# Strain_Gauge_Amplifier2.net
KiCad netlist of a schematic drawn in EAGLE
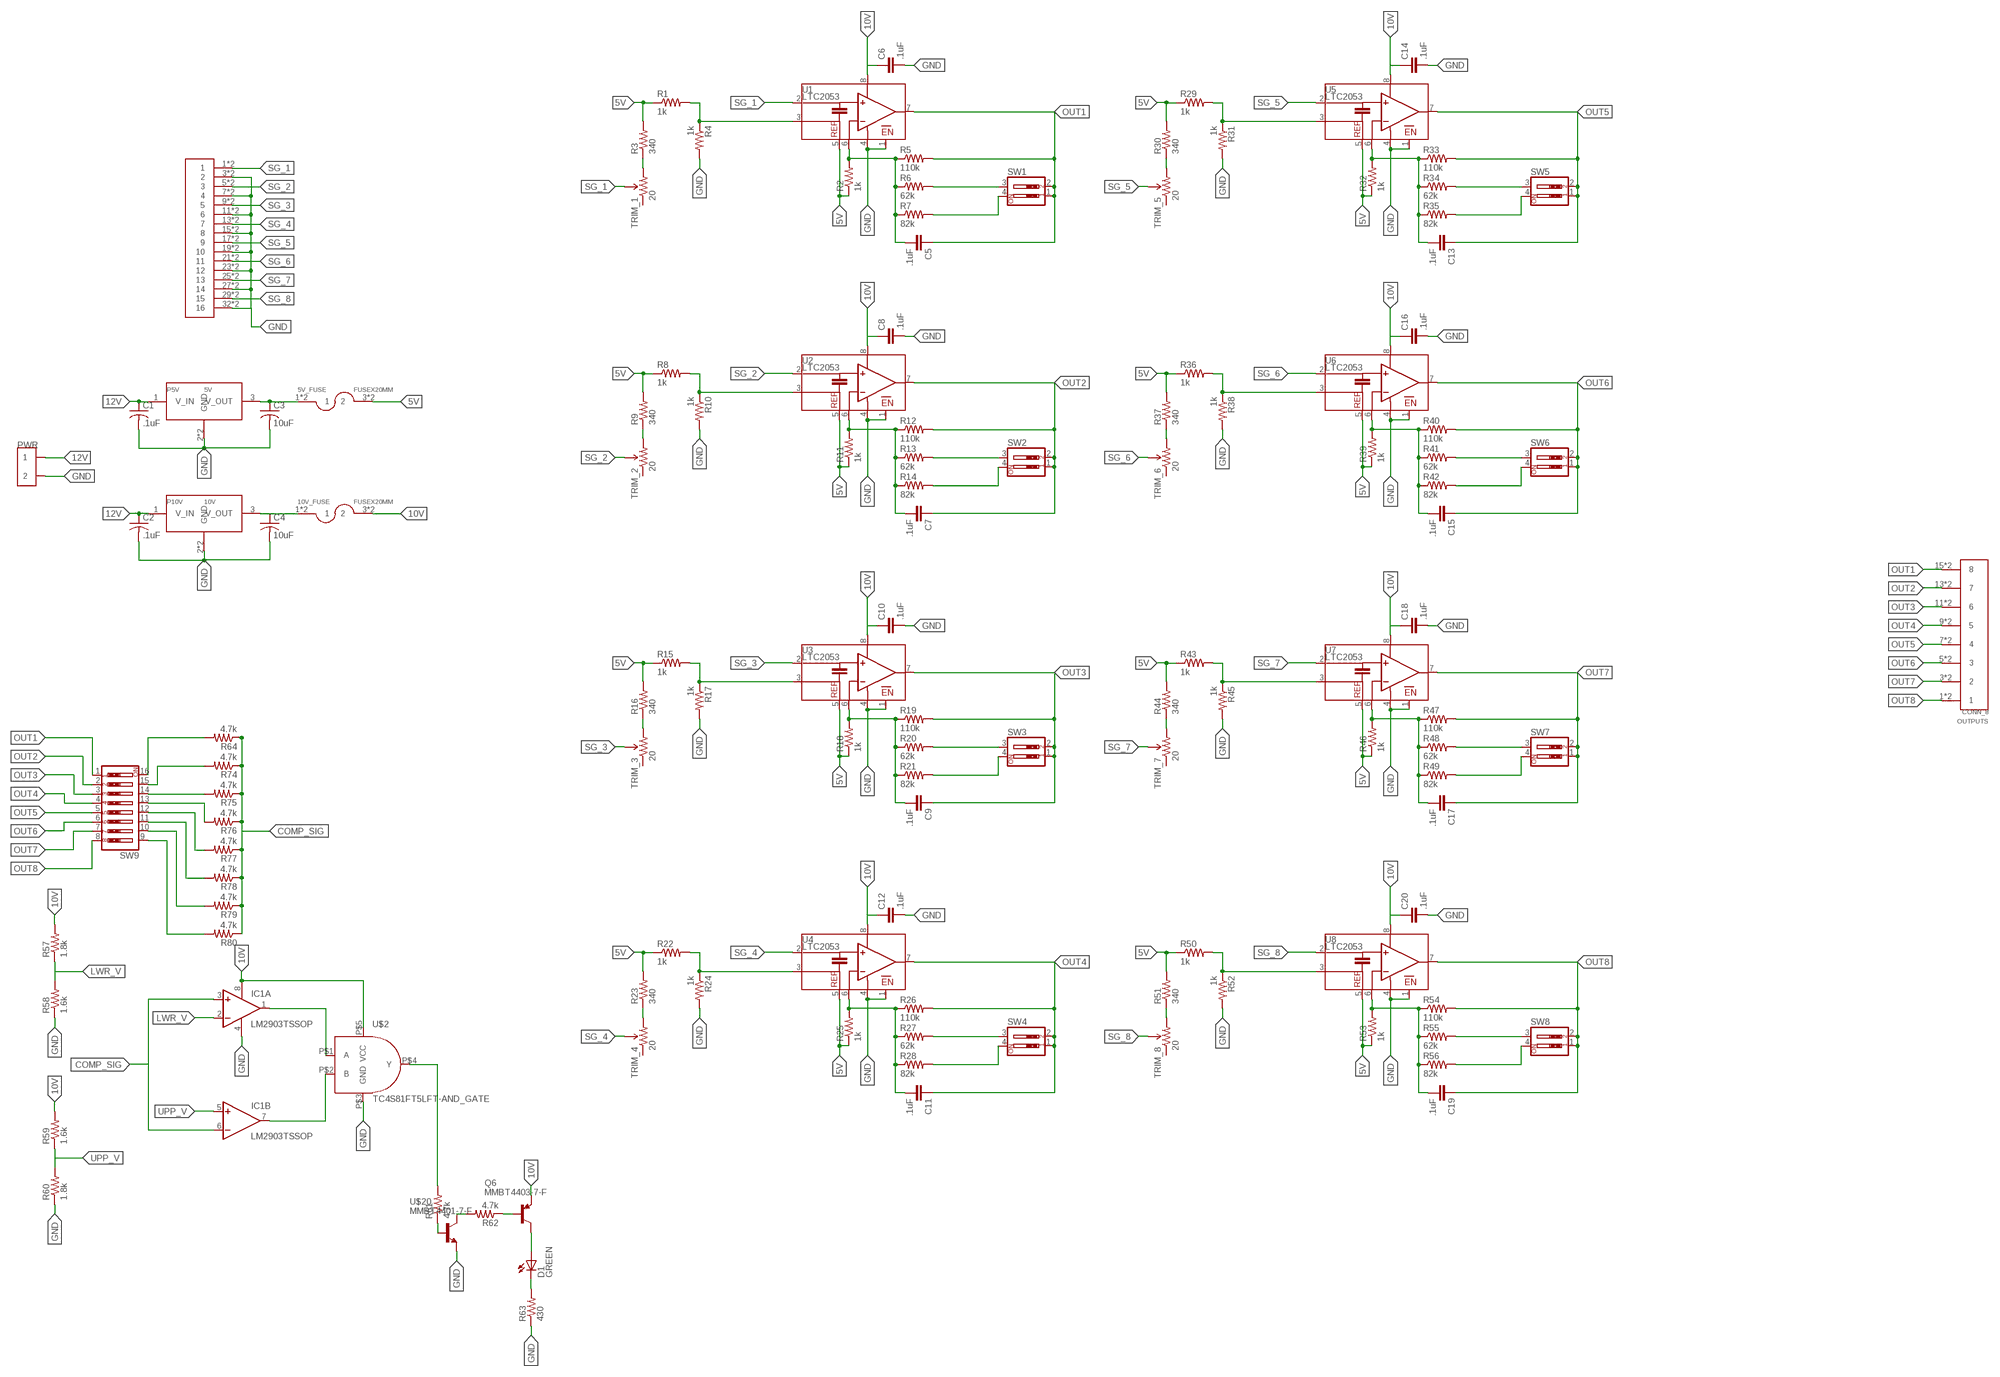
[diagram p0: schematic, sheet 1]

(export (version "E")
  (design (tool "Eeschema 10.0.6"))
  (components
    (comp (ref "5V_FUSE")
      (value "FUSEX20MM")
      (footprint "eagle-import:FUSE_5MM")
      (libsource (lib "eagle-import") (part "FUSEX20MM"))
    )
    (comp (ref "10V_FUSE")
      (value "FUSEX20MM")
      (footprint "eagle-import:FUSE_5MM")
      (libsource (lib "eagle-import") (part "FUSEX20MM"))
    )
    (comp (ref "C1")
      (value ".1uF")
      (footprint "eagle-import:C0603")
      (libsource (lib "eagle-import") (part "C-USC0603"))
    )
    (comp (ref "C2")
      (value ".1uF")
      (footprint "eagle-import:C0603")
      (libsource (lib "eagle-import") (part "C-USC0603"))
    )
    (comp (ref "C3")
      (value "10uF")
      (footprint "eagle-import:C1206")
      (libsource (lib "eagle-import") (part "C-USC1206"))
    )
    (comp (ref "C4")
      (value "10uF")
      (footprint "eagle-import:C1206")
      (libsource (lib "eagle-import") (part "C-USC1206"))
    )
    (comp (ref "C5")
      (value ".1uF")
      (footprint "eagle-import:0603-CAP")
      (libsource (lib "eagle-import") (part "CAP0603-CAP"))
    )
    (comp (ref "C6")
      (value ".1uF")
      (footprint "eagle-import:0603-CAP")
      (libsource (lib "eagle-import") (part "CAP0603-CAP"))
    )
    (comp (ref "C7")
      (value ".1uF")
      (footprint "eagle-import:0603-CAP")
      (libsource (lib "eagle-import") (part "CAP0603-CAP"))
    )
    (comp (ref "C8")
      (value ".1uF")
      (footprint "eagle-import:0603-CAP")
      (libsource (lib "eagle-import") (part "CAP0603-CAP"))
    )
    (comp (ref "C9")
      (value ".1uF")
      (footprint "eagle-import:0603-CAP")
      (libsource (lib "eagle-import") (part "CAP0603-CAP"))
    )
    (comp (ref "C10")
      (value ".1uF")
      (footprint "eagle-import:0603-CAP")
      (libsource (lib "eagle-import") (part "CAP0603-CAP"))
    )
    (comp (ref "C11")
      (value ".1uF")
      (footprint "eagle-import:0603-CAP")
      (libsource (lib "eagle-import") (part "CAP0603-CAP"))
    )
    (comp (ref "C12")
      (value ".1uF")
      (footprint "eagle-import:0603-CAP")
      (libsource (lib "eagle-import") (part "CAP0603-CAP"))
    )
    (comp (ref "C13")
      (value ".1uF")
      (footprint "eagle-import:0603-CAP")
      (libsource (lib "eagle-import") (part "CAP0603-CAP"))
    )
    (comp (ref "C14")
      (value ".1uF")
      (footprint "eagle-import:0603-CAP")
      (libsource (lib "eagle-import") (part "CAP0603-CAP"))
    )
    (comp (ref "C15")
      (value ".1uF")
      (footprint "eagle-import:0603-CAP")
      (libsource (lib "eagle-import") (part "CAP0603-CAP"))
    )
    (comp (ref "C16")
      (value ".1uF")
      (footprint "eagle-import:0603-CAP")
      (libsource (lib "eagle-import") (part "CAP0603-CAP"))
    )
    (comp (ref "C17")
      (value ".1uF")
      (footprint "eagle-import:0603-CAP")
      (libsource (lib "eagle-import") (part "CAP0603-CAP"))
    )
    (comp (ref "C18")
      (value ".1uF")
      (footprint "eagle-import:0603-CAP")
      (libsource (lib "eagle-import") (part "CAP0603-CAP"))
    )
    (comp (ref "C19")
      (value ".1uF")
      (footprint "eagle-import:0603-CAP")
      (libsource (lib "eagle-import") (part "CAP0603-CAP"))
    )
    (comp (ref "C20")
      (value ".1uF")
      (footprint "eagle-import:0603-CAP")
      (libsource (lib "eagle-import") (part "CAP0603-CAP"))
    )
    (comp (ref "D1")
      (value "GREEN")
      (footprint "eagle-import:LED-0603")
      (libsource (lib "eagle-import") (part "LED-GREEN0603"))
    )
    (comp (ref "IC1")
      (value "LM2903TSSOP")
      (footprint "eagle-import:TSSOP8")
      (libsource (lib "eagle-import") (part "LM2903TSSOP"))
    )
    (comp (ref "OUTPUTS")
      (value "CONN_8")
      (footprint "eagle-import:CONNECTOR_8")
      (libsource (lib "eagle-import") (part "CONN_8"))
    )
    (comp (ref "P5V")
      (value "5V")
      (footprint "eagle-import:SOT223")
      (libsource (lib "eagle-import") (part "LM2937"))
    )
    (comp (ref "P10V")
      (value "10V")
      (footprint "eagle-import:SOT223")
      (libsource (lib "eagle-import") (part "LM2937"))
    )
    (comp (ref "PWR")
      (value "CONN_2")
      (footprint "eagle-import:CONNECTOR_2")
      (libsource (lib "eagle-import") (part "CONN_2"))
    )
    (comp (ref "Q6")
      (value "MMBT4403-7-F")
      (footprint "eagle-import:SOT-23-3")
      (libsource (lib "eagle-import") (part "MMBT4403-7-F"))
    )
    (comp (ref "R1")
      (value "1k")
      (footprint "eagle-import:0603-RES")
      (libsource (lib "eagle-import") (part "RESISTOR0603"))
    )
    (comp (ref "R2")
      (value "1k")
      (footprint "eagle-import:0603-RES")
      (libsource (lib "eagle-import") (part "RESISTOR0603"))
    )
    (comp (ref "R3")
      (value "340")
      (footprint "eagle-import:0603-RES")
      (libsource (lib "eagle-import") (part "RESISTOR0603"))
    )
    (comp (ref "R4")
      (value "1k")
      (footprint "eagle-import:0603-RES")
      (libsource (lib "eagle-import") (part "RESISTOR0603"))
    )
    (comp (ref "R5")
      (value "110k")
      (footprint "eagle-import:0603-RES")
      (libsource (lib "eagle-import") (part "RESISTOR0603"))
    )
    (comp (ref "R6")
      (value "62k")
      (footprint "eagle-import:0603-RES")
      (libsource (lib "eagle-import") (part "RESISTOR0603"))
    )
    (comp (ref "R7")
      (value "82k")
      (footprint "eagle-import:0603-RES")
      (libsource (lib "eagle-import") (part "RESISTOR0603"))
    )
    (comp (ref "R8")
      (value "1k")
      (footprint "eagle-import:0603-RES")
      (libsource (lib "eagle-import") (part "RESISTOR0603"))
    )
    (comp (ref "R9")
      (value "340")
      (footprint "eagle-import:0603-RES")
      (libsource (lib "eagle-import") (part "RESISTOR0603"))
    )
    (comp (ref "R10")
      (value "1k")
      (footprint "eagle-import:0603-RES")
      (libsource (lib "eagle-import") (part "RESISTOR0603"))
    )
    (comp (ref "R11")
      (value "1k")
      (footprint "eagle-import:0603-RES")
      (libsource (lib "eagle-import") (part "RESISTOR0603"))
    )
    (comp (ref "R12")
      (value "110k")
      (footprint "eagle-import:0603-RES")
      (libsource (lib "eagle-import") (part "RESISTOR0603"))
    )
    (comp (ref "R13")
      (value "62k")
      (footprint "eagle-import:0603-RES")
      (libsource (lib "eagle-import") (part "RESISTOR0603"))
    )
    (comp (ref "R14")
      (value "82k")
      (footprint "eagle-import:0603-RES")
      (libsource (lib "eagle-import") (part "RESISTOR0603"))
    )
    (comp (ref "R15")
      (value "1k")
      (footprint "eagle-import:0603-RES")
      (libsource (lib "eagle-import") (part "RESISTOR0603"))
    )
    (comp (ref "R16")
      (value "340")
      (footprint "eagle-import:0603-RES")
      (libsource (lib "eagle-import") (part "RESISTOR0603"))
    )
    (comp (ref "R17")
      (value "1k")
      (footprint "eagle-import:0603-RES")
      (libsource (lib "eagle-import") (part "RESISTOR0603"))
    )
    (comp (ref "R18")
      (value "1k")
      (footprint "eagle-import:0603-RES")
      (libsource (lib "eagle-import") (part "RESISTOR0603"))
    )
    (comp (ref "R19")
      (value "110k")
      (footprint "eagle-import:0603-RES")
      (libsource (lib "eagle-import") (part "RESISTOR0603"))
    )
    (comp (ref "R20")
      (value "62k")
      (footprint "eagle-import:0603-RES")
      (libsource (lib "eagle-import") (part "RESISTOR0603"))
    )
    (comp (ref "R21")
      (value "82k")
      (footprint "eagle-import:0603-RES")
      (libsource (lib "eagle-import") (part "RESISTOR0603"))
    )
    (comp (ref "R22")
      (value "1k")
      (footprint "eagle-import:0603-RES")
      (libsource (lib "eagle-import") (part "RESISTOR0603"))
    )
    (comp (ref "R23")
      (value "340")
      (footprint "eagle-import:0603-RES")
      (libsource (lib "eagle-import") (part "RESISTOR0603"))
    )
    (comp (ref "R24")
      (value "1k")
      (footprint "eagle-import:0603-RES")
      (libsource (lib "eagle-import") (part "RESISTOR0603"))
    )
    (comp (ref "R25")
      (value "1k")
      (footprint "eagle-import:0603-RES")
      (libsource (lib "eagle-import") (part "RESISTOR0603"))
    )
    (comp (ref "R26")
      (value "110k")
      (footprint "eagle-import:0603-RES")
      (libsource (lib "eagle-import") (part "RESISTOR0603"))
    )
    (comp (ref "R27")
      (value "62k")
      (footprint "eagle-import:0603-RES")
      (libsource (lib "eagle-import") (part "RESISTOR0603"))
    )
    (comp (ref "R28")
      (value "82k")
      (footprint "eagle-import:0603-RES")
      (libsource (lib "eagle-import") (part "RESISTOR0603"))
    )
    (comp (ref "R29")
      (value "1k")
      (footprint "eagle-import:0603-RES")
      (libsource (lib "eagle-import") (part "RESISTOR0603"))
    )
    (comp (ref "R30")
      (value "340")
      (footprint "eagle-import:0603-RES")
      (libsource (lib "eagle-import") (part "RESISTOR0603"))
    )
    (comp (ref "R31")
      (value "1k")
      (footprint "eagle-import:0603-RES")
      (libsource (lib "eagle-import") (part "RESISTOR0603"))
    )
    (comp (ref "R32")
      (value "1k")
      (footprint "eagle-import:0603-RES")
      (libsource (lib "eagle-import") (part "RESISTOR0603"))
    )
    (comp (ref "R33")
      (value "110k")
      (footprint "eagle-import:0603-RES")
      (libsource (lib "eagle-import") (part "RESISTOR0603"))
    )
    (comp (ref "R34")
      (value "62k")
      (footprint "eagle-import:0603-RES")
      (libsource (lib "eagle-import") (part "RESISTOR0603"))
    )
    (comp (ref "R35")
      (value "82k")
      (footprint "eagle-import:0603-RES")
      (libsource (lib "eagle-import") (part "RESISTOR0603"))
    )
    (comp (ref "R36")
      (value "1k")
      (footprint "eagle-import:0603-RES")
      (libsource (lib "eagle-import") (part "RESISTOR0603"))
    )
    (comp (ref "R37")
      (value "340")
      (footprint "eagle-import:0603-RES")
      (libsource (lib "eagle-import") (part "RESISTOR0603"))
    )
    (comp (ref "R38")
      (value "1k")
      (footprint "eagle-import:0603-RES")
      (libsource (lib "eagle-import") (part "RESISTOR0603"))
    )
    (comp (ref "R39")
      (value "1k")
      (footprint "eagle-import:0603-RES")
      (libsource (lib "eagle-import") (part "RESISTOR0603"))
    )
    (comp (ref "R40")
      (value "110k")
      (footprint "eagle-import:0603-RES")
      (libsource (lib "eagle-import") (part "RESISTOR0603"))
    )
    (comp (ref "R41")
      (value "62k")
      (footprint "eagle-import:0603-RES")
      (libsource (lib "eagle-import") (part "RESISTOR0603"))
    )
    (comp (ref "R42")
      (value "82k")
      (footprint "eagle-import:0603-RES")
      (libsource (lib "eagle-import") (part "RESISTOR0603"))
    )
    (comp (ref "R43")
      (value "1k")
      (footprint "eagle-import:0603-RES")
      (libsource (lib "eagle-import") (part "RESISTOR0603"))
    )
    (comp (ref "R44")
      (value "340")
      (footprint "eagle-import:0603-RES")
      (libsource (lib "eagle-import") (part "RESISTOR0603"))
    )
    (comp (ref "R45")
      (value "1k")
      (footprint "eagle-import:0603-RES")
      (libsource (lib "eagle-import") (part "RESISTOR0603"))
    )
    (comp (ref "R46")
      (value "1k")
      (footprint "eagle-import:0603-RES")
      (libsource (lib "eagle-import") (part "RESISTOR0603"))
    )
    (comp (ref "R47")
      (value "110k")
      (footprint "eagle-import:0603-RES")
      (libsource (lib "eagle-import") (part "RESISTOR0603"))
    )
    (comp (ref "R48")
      (value "62k")
      (footprint "eagle-import:0603-RES")
      (libsource (lib "eagle-import") (part "RESISTOR0603"))
    )
    (comp (ref "R49")
      (value "82k")
      (footprint "eagle-import:0603-RES")
      (libsource (lib "eagle-import") (part "RESISTOR0603"))
    )
    (comp (ref "R50")
      (value "1k")
      (footprint "eagle-import:0603-RES")
      (libsource (lib "eagle-import") (part "RESISTOR0603"))
    )
    (comp (ref "R51")
      (value "340")
      (footprint "eagle-import:0603-RES")
      (libsource (lib "eagle-import") (part "RESISTOR0603"))
    )
    (comp (ref "R52")
      (value "1k")
      (footprint "eagle-import:0603-RES")
      (libsource (lib "eagle-import") (part "RESISTOR0603"))
    )
    (comp (ref "R53")
      (value "1k")
      (footprint "eagle-import:0603-RES")
      (libsource (lib "eagle-import") (part "RESISTOR0603"))
    )
    (comp (ref "R54")
      (value "110k")
      (footprint "eagle-import:0603-RES")
      (libsource (lib "eagle-import") (part "RESISTOR0603"))
    )
    (comp (ref "R55")
      (value "62k")
      (footprint "eagle-import:0603-RES")
      (libsource (lib "eagle-import") (part "RESISTOR0603"))
    )
    (comp (ref "R56")
      (value "82k")
      (footprint "eagle-import:0603-RES")
      (libsource (lib "eagle-import") (part "RESISTOR0603"))
    )
    (comp (ref "R57")
      (value "1.8k")
      (footprint "eagle-import:0603-RES")
      (libsource (lib "eagle-import") (part "RESISTOR0603"))
    )
    (comp (ref "R58")
      (value "1.6k")
      (footprint "eagle-import:0603-RES")
      (libsource (lib "eagle-import") (part "RESISTOR0603"))
    )
    (comp (ref "R59")
      (value "1.6k")
      (footprint "eagle-import:0603-RES")
      (libsource (lib "eagle-import") (part "RESISTOR0603"))
    )
    (comp (ref "R60")
      (value "1.8k")
      (footprint "eagle-import:0603-RES")
      (libsource (lib "eagle-import") (part "RESISTOR0603"))
    )
    (comp (ref "R61")
      (value "4.7k")
      (footprint "eagle-import:0603-RES")
      (libsource (lib "eagle-import") (part "RESISTOR0603"))
    )
    (comp (ref "R62")
      (value "4.7k")
      (footprint "eagle-import:0603-RES")
      (libsource (lib "eagle-import") (part "RESISTOR0603"))
    )
    (comp (ref "R63")
      (value "430")
      (footprint "eagle-import:0603-RES")
      (libsource (lib "eagle-import") (part "RESISTOR0603"))
    )
    (comp (ref "R64")
      (value "4.7k")
      (footprint "eagle-import:0603-RES")
      (libsource (lib "eagle-import") (part "RESISTOR0603"))
    )
    (comp (ref "R74")
      (value "4.7k")
      (footprint "eagle-import:0603-RES")
      (libsource (lib "eagle-import") (part "RESISTOR0603"))
    )
    (comp (ref "R75")
      (value "4.7k")
      (footprint "eagle-import:0603-RES")
      (libsource (lib "eagle-import") (part "RESISTOR0603"))
    )
    (comp (ref "R76")
      (value "4.7k")
      (footprint "eagle-import:0603-RES")
      (libsource (lib "eagle-import") (part "RESISTOR0603"))
    )
    (comp (ref "R77")
      (value "4.7k")
      (footprint "eagle-import:0603-RES")
      (libsource (lib "eagle-import") (part "RESISTOR0603"))
    )
    (comp (ref "R78")
      (value "4.7k")
      (footprint "eagle-import:0603-RES")
      (libsource (lib "eagle-import") (part "RESISTOR0603"))
    )
    (comp (ref "R79")
      (value "4.7k")
      (footprint "eagle-import:0603-RES")
      (libsource (lib "eagle-import") (part "RESISTOR0603"))
    )
    (comp (ref "R80")
      (value "4.7k")
      (footprint "eagle-import:0603-RES")
      (libsource (lib "eagle-import") (part "RESISTOR0603"))
    )
    (comp (ref "SG_CONN")
      (value "CONN_16")
      (footprint "eagle-import:CONNECTOR_16")
      (libsource (lib "eagle-import") (part "CONN_16"))
    )
    (comp (ref "SW1")
      (value "SW_DIP-2")
      (footprint "eagle-import:DIPSWITCH-02")
      (libsource (lib "eagle-import") (part "SW_DIP-2"))
    )
    (comp (ref "SW2")
      (value "SW_DIP-2")
      (footprint "eagle-import:DIPSWITCH-02")
      (libsource (lib "eagle-import") (part "SW_DIP-2"))
    )
    (comp (ref "SW3")
      (value "SW_DIP-2")
      (footprint "eagle-import:DIPSWITCH-02")
      (libsource (lib "eagle-import") (part "SW_DIP-2"))
    )
    (comp (ref "SW4")
      (value "SW_DIP-2")
      (footprint "eagle-import:DIPSWITCH-02")
      (libsource (lib "eagle-import") (part "SW_DIP-2"))
    )
    (comp (ref "SW5")
      (value "SW_DIP-2")
      (footprint "eagle-import:DIPSWITCH-02")
      (libsource (lib "eagle-import") (part "SW_DIP-2"))
    )
    (comp (ref "SW6")
      (value "SW_DIP-2")
      (footprint "eagle-import:DIPSWITCH-02")
      (libsource (lib "eagle-import") (part "SW_DIP-2"))
    )
    (comp (ref "SW7")
      (value "SW_DIP-2")
      (footprint "eagle-import:DIPSWITCH-02")
      (libsource (lib "eagle-import") (part "SW_DIP-2"))
    )
    (comp (ref "SW8")
      (value "SW_DIP-2")
      (footprint "eagle-import:DIPSWITCH-02")
      (libsource (lib "eagle-import") (part "SW_DIP-2"))
    )
    (comp (ref "SW9")
      (value "SW_DIP-8")
      (footprint "eagle-import:DIPSWITCH-08")
      (libsource (lib "eagle-import") (part "SW_DIP-8"))
    )
    (comp (ref "TRIM_1")
      (value "20")
      (footprint "eagle-import:3926_Y,Z")
      (libsource (lib "eagle-import") (part "3296Y"))
    )
    (comp (ref "TRIM_2")
      (value "20")
      (footprint "eagle-import:3926_Y,Z")
      (libsource (lib "eagle-import") (part "3296Y"))
    )
    (comp (ref "TRIM_3")
      (value "20")
      (footprint "eagle-import:3926_Y,Z")
      (libsource (lib "eagle-import") (part "3296Y"))
    )
    (comp (ref "TRIM_4")
      (value "20")
      (footprint "eagle-import:3926_Y,Z")
      (libsource (lib "eagle-import") (part "3296Y"))
    )
    (comp (ref "TRIM_5")
      (value "20")
      (footprint "eagle-import:3926_Y,Z")
      (libsource (lib "eagle-import") (part "3296Y"))
    )
    (comp (ref "TRIM_6")
      (value "20")
      (footprint "eagle-import:3926_Y,Z")
      (libsource (lib "eagle-import") (part "3296Y"))
    )
    (comp (ref "TRIM_7")
      (value "20")
      (footprint "eagle-import:3926_Y,Z")
      (libsource (lib "eagle-import") (part "3296Y"))
    )
    (comp (ref "TRIM_8")
      (value "20")
      (footprint "eagle-import:3926_Y,Z")
      (libsource (lib "eagle-import") (part "3296Y"))
    )
    (comp (ref "U$2")
      (value "TC4S81FT5LFT-AND_GATE")
      (footprint "eagle-import:SSOP5-P-0.95")
      (libsource (lib "eagle-import") (part "TC4S81FT5LFT-AND_GATE"))
    )
    (comp (ref "U$20")
      (value "MMBT4401-7-F")
      (footprint "eagle-import:SOT-23-3")
      (libsource (lib "eagle-import") (part "MMBT4401-7-F"))
    )
    (comp (ref "U1")
      (value "LTC2053")
      (footprint "eagle-import:MSOP8")
      (libsource (lib "eagle-import") (part "LTC2053"))
    )
    (comp (ref "U2")
      (value "LTC2053")
      (footprint "eagle-import:MSOP8")
      (libsource (lib "eagle-import") (part "LTC2053"))
    )
    (comp (ref "U3")
      (value "LTC2053")
      (footprint "eagle-import:MSOP8")
      (libsource (lib "eagle-import") (part "LTC2053"))
    )
    (comp (ref "U4")
      (value "LTC2053")
      (footprint "eagle-import:MSOP8")
      (libsource (lib "eagle-import") (part "LTC2053"))
    )
    (comp (ref "U5")
      (value "LTC2053")
      (footprint "eagle-import:MSOP8")
      (libsource (lib "eagle-import") (part "LTC2053"))
    )
    (comp (ref "U6")
      (value "LTC2053")
      (footprint "eagle-import:MSOP8")
      (libsource (lib "eagle-import") (part "LTC2053"))
    )
    (comp (ref "U7")
      (value "LTC2053")
      (footprint "eagle-import:MSOP8")
      (libsource (lib "eagle-import") (part "LTC2053"))
    )
    (comp (ref "U8")
      (value "LTC2053")
      (footprint "eagle-import:MSOP8")
      (libsource (lib "eagle-import") (part "LTC2053"))
    )
  )
  (nets
    (net (code "1") (name "5V") (class "Default")
      (node (ref "5V_FUSE") (pin "3") (pinfunction "2_3") (pintype "bidirectional"))
      (node (ref "5V_FUSE") (pin "4") (pinfunction "2_4") (pintype "bidirectional"))
      (node (ref "R1") (pin "1") (pinfunction "1_1") (pintype "passive"))
      (node (ref "R11") (pin "1") (pinfunction "1_1") (pintype "passive"))
      (node (ref "R15") (pin "1") (pinfunction "1_1") (pintype "passive"))
      (node (ref "R16") (pin "2") (pinfunction "2_2") (pintype "passive"))
      (node (ref "R18") (pin "1") (pinfunction "1_1") (pintype "passive"))
      (node (ref "R2") (pin "1") (pinfunction "1_1") (pintype "passive"))
      (node (ref "R22") (pin "1") (pinfunction "1_1") (pintype "passive"))
      (node (ref "R23") (pin "2") (pinfunction "2_2") (pintype "passive"))
      (node (ref "R25") (pin "1") (pinfunction "1_1") (pintype "passive"))
      (node (ref "R29") (pin "1") (pinfunction "1_1") (pintype "passive"))
      (node (ref "R3") (pin "2") (pinfunction "2_2") (pintype "passive"))
      (node (ref "R30") (pin "2") (pinfunction "2_2") (pintype "passive"))
      (node (ref "R32") (pin "1") (pinfunction "1_1") (pintype "passive"))
      (node (ref "R36") (pin "1") (pinfunction "1_1") (pintype "passive"))
      (node (ref "R37") (pin "2") (pinfunction "2_2") (pintype "passive"))
      (node (ref "R39") (pin "1") (pinfunction "1_1") (pintype "passive"))
      (node (ref "R43") (pin "1") (pinfunction "1_1") (pintype "passive"))
      (node (ref "R44") (pin "2") (pinfunction "2_2") (pintype "passive"))
      (node (ref "R46") (pin "1") (pinfunction "1_1") (pintype "passive"))
      (node (ref "R50") (pin "1") (pinfunction "1_1") (pintype "passive"))
      (node (ref "R51") (pin "2") (pinfunction "2_2") (pintype "passive"))
      (node (ref "R53") (pin "1") (pinfunction "1_1") (pintype "passive"))
      (node (ref "R8") (pin "1") (pinfunction "1_1") (pintype "passive"))
      (node (ref "R9") (pin "2") (pinfunction "2_2") (pintype "passive"))
      (node (ref "U1") (pin "5") (pinfunction "REF_5") (pintype "bidirectional"))
      (node (ref "U2") (pin "5") (pinfunction "REF_5") (pintype "bidirectional"))
      (node (ref "U3") (pin "5") (pinfunction "REF_5") (pintype "bidirectional"))
      (node (ref "U4") (pin "5") (pinfunction "REF_5") (pintype "bidirectional"))
      (node (ref "U5") (pin "5") (pinfunction "REF_5") (pintype "bidirectional"))
      (node (ref "U6") (pin "5") (pinfunction "REF_5") (pintype "bidirectional"))
      (node (ref "U7") (pin "5") (pinfunction "REF_5") (pintype "bidirectional"))
      (node (ref "U8") (pin "5") (pinfunction "REF_5") (pintype "bidirectional"))
    )
    (net (code "2") (name "10V") (class "Default")
      (node (ref "10V_FUSE") (pin "3") (pinfunction "2_3") (pintype "bidirectional"))
      (node (ref "10V_FUSE") (pin "4") (pinfunction "2_4") (pintype "bidirectional"))
      (node (ref "C10") (pin "1") (pinfunction "1_1") (pintype "passive"))
      (node (ref "C12") (pin "1") (pinfunction "1_1") (pintype "passive"))
      (node (ref "C14") (pin "1") (pinfunction "1_1") (pintype "passive"))
      (node (ref "C16") (pin "1") (pinfunction "1_1") (pintype "passive"))
      (node (ref "C18") (pin "1") (pinfunction "1_1") (pintype "passive"))
      (node (ref "C20") (pin "1") (pinfunction "1_1") (pintype "passive"))
      (node (ref "C6") (pin "1") (pinfunction "1_1") (pintype "passive"))
      (node (ref "C8") (pin "1") (pinfunction "1_1") (pintype "passive"))
      (node (ref "IC1") (pin "8") (pinfunction "V+_8") (pintype "power_in"))
      (node (ref "Q6") (pin "P$3") (pinfunction "E_P$3") (pintype "passive"))
      (node (ref "R57") (pin "2") (pinfunction "2_2") (pintype "passive"))
      (node (ref "R59") (pin "2") (pinfunction "2_2") (pintype "passive"))
      (node (ref "U$2") (pin "P$5") (pinfunction "VCC_P$5") (pintype "bidirectional"))
      (node (ref "U1") (pin "8") (pinfunction "V+_8") (pintype "power_in"))
      (node (ref "U2") (pin "8") (pinfunction "V+_8") (pintype "power_in"))
      (node (ref "U3") (pin "8") (pinfunction "V+_8") (pintype "power_in"))
      (node (ref "U4") (pin "8") (pinfunction "V+_8") (pintype "power_in"))
      (node (ref "U5") (pin "8") (pinfunction "V+_8") (pintype "power_in"))
      (node (ref "U6") (pin "8") (pinfunction "V+_8") (pintype "power_in"))
      (node (ref "U7") (pin "8") (pinfunction "V+_8") (pintype "power_in"))
      (node (ref "U8") (pin "8") (pinfunction "V+_8") (pintype "power_in"))
    )
    (net (code "3") (name "12V") (class "Default")
      (node (ref "C1") (pin "1") (pinfunction "1_1") (pintype "passive"))
      (node (ref "C2") (pin "1") (pinfunction "1_1") (pintype "passive"))
      (node (ref "P10V") (pin "1") (pinfunction "V_IN_1") (pintype "power_in"))
      (node (ref "P5V") (pin "1") (pinfunction "V_IN_1") (pintype "power_in"))
      (node (ref "PWR") (pin "1") (pinfunction "1_1") (pintype "bidirectional"))
      (node (ref "PWR") (pin "2") (pinfunction "1_2") (pintype "bidirectional"))
    )
    (net (code "4") (name "COMP_SIG") (class "Default")
      (node (ref "IC1") (pin "3") (pinfunction "+IN_3") (pintype "input"))
      (node (ref "IC1") (pin "6") (pinfunction "-IN_6") (pintype "input"))
      (node (ref "R64") (pin "1") (pinfunction "1_1") (pintype "passive"))
      (node (ref "R74") (pin "1") (pinfunction "1_1") (pintype "passive"))
      (node (ref "R75") (pin "1") (pinfunction "1_1") (pintype "passive"))
      (node (ref "R76") (pin "1") (pinfunction "1_1") (pintype "passive"))
      (node (ref "R77") (pin "1") (pinfunction "1_1") (pintype "passive"))
      (node (ref "R78") (pin "1") (pinfunction "1_1") (pintype "passive"))
      (node (ref "R79") (pin "1") (pinfunction "1_1") (pintype "passive"))
      (node (ref "R80") (pin "1") (pinfunction "1_1") (pintype "passive"))
    )
    (net (code "5") (name "GND") (class "Default")
      (node (ref "C1") (pin "2") (pinfunction "2_2") (pintype "passive"))
      (node (ref "C10") (pin "2") (pinfunction "2_2") (pintype "passive"))
      (node (ref "C12") (pin "2") (pinfunction "2_2") (pintype "passive"))
      (node (ref "C14") (pin "2") (pinfunction "2_2") (pintype "passive"))
      (node (ref "C16") (pin "2") (pinfunction "2_2") (pintype "passive"))
      (node (ref "C18") (pin "2") (pinfunction "2_2") (pintype "passive"))
      (node (ref "C2") (pin "2") (pinfunction "2_2") (pintype "passive"))
      (node (ref "C20") (pin "2") (pinfunction "2_2") (pintype "passive"))
      (node (ref "C3") (pin "2") (pinfunction "2_2") (pintype "passive"))
      (node (ref "C4") (pin "2") (pinfunction "2_2") (pintype "passive"))
      (node (ref "C6") (pin "2") (pinfunction "2_2") (pintype "passive"))
      (node (ref "C8") (pin "2") (pinfunction "2_2") (pintype "passive"))
      (node (ref "IC1") (pin "4") (pinfunction "V-_4") (pintype "power_in"))
      (node (ref "P10V") (pin "2") (pinfunction "GND_2") (pintype "power_in"))
      (node (ref "P10V") (pin "4") (pinfunction "GND_4") (pintype "power_in"))
      (node (ref "P5V") (pin "2") (pinfunction "GND_2") (pintype "power_in"))
      (node (ref "P5V") (pin "4") (pinfunction "GND_4") (pintype "power_in"))
      (node (ref "PWR") (pin "3") (pinfunction "2_3") (pintype "bidirectional"))
      (node (ref "PWR") (pin "4") (pinfunction "2_4") (pintype "bidirectional"))
      (node (ref "R10") (pin "2") (pinfunction "2_2") (pintype "passive"))
      (node (ref "R17") (pin "2") (pinfunction "2_2") (pintype "passive"))
      (node (ref "R24") (pin "2") (pinfunction "2_2") (pintype "passive"))
      (node (ref "R31") (pin "2") (pinfunction "2_2") (pintype "passive"))
      (node (ref "R38") (pin "2") (pinfunction "2_2") (pintype "passive"))
      (node (ref "R4") (pin "2") (pinfunction "2_2") (pintype "passive"))
      (node (ref "R45") (pin "2") (pinfunction "2_2") (pintype "passive"))
      (node (ref "R52") (pin "2") (pinfunction "2_2") (pintype "passive"))
      (node (ref "R58") (pin "1") (pinfunction "1_1") (pintype "passive"))
      (node (ref "R60") (pin "1") (pinfunction "1_1") (pintype "passive"))
      (node (ref "R63") (pin "1") (pinfunction "1_1") (pintype "passive"))
      (node (ref "SG_CONN") (pin "11") (pinfunction "6_11") (pintype "bidirectional"))
      (node (ref "SG_CONN") (pin "12") (pinfunction "6_12") (pintype "bidirectional"))
      (node (ref "SG_CONN") (pin "15") (pinfunction "8_15") (pintype "bidirectional"))
      (node (ref "SG_CONN") (pin "16") (pinfunction "8_16") (pintype "bidirectional"))
      (node (ref "SG_CONN") (pin "19") (pinfunction "10_19") (pintype "bidirectional"))
      (node (ref "SG_CONN") (pin "20") (pinfunction "10_20") (pintype "bidirectional"))
      (node (ref "SG_CONN") (pin "23") (pinfunction "12_23") (pintype "bidirectional"))
      (node (ref "SG_CONN") (pin "24") (pinfunction "12_24") (pintype "bidirectional"))
      (node (ref "SG_CONN") (pin "27") (pinfunction "14_27") (pintype "bidirectional"))
      (node (ref "SG_CONN") (pin "28") (pinfunction "14_28") (pintype "bidirectional"))
      (node (ref "SG_CONN") (pin "3") (pinfunction "2_3") (pintype "bidirectional"))
      (node (ref "SG_CONN") (pin "32") (pinfunction "16_32") (pintype "bidirectional"))
      (node (ref "SG_CONN") (pin "4") (pinfunction "2_4") (pintype "bidirectional"))
      (node (ref "SG_CONN") (pin "7") (pinfunction "4_7") (pintype "bidirectional"))
      (node (ref "SG_CONN") (pin "8") (pinfunction "4_8") (pintype "bidirectional"))
      (node (ref "SG_CONN") (pin "P31") (pinfunction "16_P31") (pintype "bidirectional"))
      (node (ref "U$2") (pin "P$3") (pinfunction "GND_P$3") (pintype "bidirectional"))
      (node (ref "U$20") (pin "P$3") (pinfunction "E_P$3") (pintype "passive"))
      (node (ref "U1") (pin "1") (pinfunction "EN_1") (pintype "input"))
      (node (ref "U1") (pin "4") (pinfunction "V-_4") (pintype "power_in"))
      (node (ref "U2") (pin "1") (pinfunction "EN_1") (pintype "input"))
      (node (ref "U2") (pin "4") (pinfunction "V-_4") (pintype "power_in"))
      (node (ref "U3") (pin "1") (pinfunction "EN_1") (pintype "input"))
      (node (ref "U3") (pin "4") (pinfunction "V-_4") (pintype "power_in"))
      (node (ref "U4") (pin "1") (pinfunction "EN_1") (pintype "input"))
      (node (ref "U4") (pin "4") (pinfunction "V-_4") (pintype "power_in"))
      (node (ref "U5") (pin "1") (pinfunction "EN_1") (pintype "input"))
      (node (ref "U5") (pin "4") (pinfunction "V-_4") (pintype "power_in"))
      (node (ref "U6") (pin "1") (pinfunction "EN_1") (pintype "input"))
      (node (ref "U6") (pin "4") (pinfunction "V-_4") (pintype "power_in"))
      (node (ref "U7") (pin "1") (pinfunction "EN_1") (pintype "input"))
      (node (ref "U7") (pin "4") (pinfunction "V-_4") (pintype "power_in"))
      (node (ref "U8") (pin "1") (pinfunction "EN_1") (pintype "input"))
      (node (ref "U8") (pin "4") (pinfunction "V-_4") (pintype "power_in"))
    )
    (net (code "6") (name "LWR_V") (class "Default")
      (node (ref "IC1") (pin "2") (pinfunction "-IN_2") (pintype "input"))
      (node (ref "R57") (pin "1") (pinfunction "1_1") (pintype "passive"))
      (node (ref "R58") (pin "2") (pinfunction "2_2") (pintype "passive"))
    )
    (net (code "7") (name "Net-(D1-PadC)") (class "Default")
      (node (ref "D1") (pin "C") (pinfunction "C_C") (pintype "passive"))
      (node (ref "R63") (pin "2") (pinfunction "2_2") (pintype "passive"))
    )
    (net (code "8") (name "Net-(IC1A-OUT)") (class "Default")
      (node (ref "IC1") (pin "1") (pinfunction "OUT_1") (pintype "output"))
      (node (ref "U$2") (pin "P$1") (pinfunction "A_P$1") (pintype "bidirectional"))
    )
    (net (code "9") (name "Net-(IC1B-OUT)") (class "Default")
      (node (ref "IC1") (pin "7") (pinfunction "OUT_7") (pintype "output"))
      (node (ref "U$2") (pin "P$2") (pinfunction "B_P$2") (pintype "bidirectional"))
    )
    (net (code "10") (name "Net-(P5V-V_OUT)") (class "Default")
      (node (ref "5V_FUSE") (pin "1") (pinfunction "1_1") (pintype "bidirectional"))
      (node (ref "5V_FUSE") (pin "2") (pinfunction "1_2") (pintype "bidirectional"))
      (node (ref "C3") (pin "1") (pinfunction "1_1") (pintype "passive"))
      (node (ref "P5V") (pin "3") (pinfunction "V_OUT_3") (pintype "output"))
    )
    (net (code "11") (name "Net-(P10V-V_OUT)") (class "Default")
      (node (ref "10V_FUSE") (pin "1") (pinfunction "1_1") (pintype "bidirectional"))
      (node (ref "10V_FUSE") (pin "2") (pinfunction "1_2") (pintype "bidirectional"))
      (node (ref "C4") (pin "1") (pinfunction "1_1") (pintype "passive"))
      (node (ref "P10V") (pin "3") (pinfunction "V_OUT_3") (pintype "output"))
    )
    (net (code "12") (name "Net-(Q6-B)") (class "Default")
      (node (ref "Q6") (pin "P$2") (pinfunction "B_P$2") (pintype "passive"))
      (node (ref "R62") (pin "1") (pinfunction "1_1") (pintype "passive"))
    )
    (net (code "13") (name "Net-(Q6-C)") (class "Default")
      (node (ref "D1") (pin "A") (pinfunction "A_A") (pintype "passive"))
      (node (ref "Q6") (pin "P$1") (pinfunction "C_P$1") (pintype "passive"))
    )
    (net (code "14") (name "Net-(R6-Pad2)") (class "Default")
      (node (ref "R6") (pin "2") (pinfunction "2_2") (pintype "passive"))
      (node (ref "SW1") (pin "3") (pinfunction "3_3") (pintype "passive"))
    )
    (net (code "15") (name "Net-(R7-Pad2)") (class "Default")
      (node (ref "R7") (pin "2") (pinfunction "2_2") (pintype "passive"))
      (node (ref "SW1") (pin "4") (pinfunction "4_4") (pintype "passive"))
    )
    (net (code "16") (name "Net-(R13-Pad2)") (class "Default")
      (node (ref "R13") (pin "2") (pinfunction "2_2") (pintype "passive"))
      (node (ref "SW2") (pin "3") (pinfunction "3_3") (pintype "passive"))
    )
    (net (code "17") (name "Net-(R14-Pad2)") (class "Default")
      (node (ref "R14") (pin "2") (pinfunction "2_2") (pintype "passive"))
      (node (ref "SW2") (pin "4") (pinfunction "4_4") (pintype "passive"))
    )
    (net (code "18") (name "Net-(R20-Pad2)") (class "Default")
      (node (ref "R20") (pin "2") (pinfunction "2_2") (pintype "passive"))
      (node (ref "SW3") (pin "3") (pinfunction "3_3") (pintype "passive"))
    )
    (net (code "19") (name "Net-(R21-Pad2)") (class "Default")
      (node (ref "R21") (pin "2") (pinfunction "2_2") (pintype "passive"))
      (node (ref "SW3") (pin "4") (pinfunction "4_4") (pintype "passive"))
    )
    (net (code "20") (name "Net-(R27-Pad2)") (class "Default")
      (node (ref "R27") (pin "2") (pinfunction "2_2") (pintype "passive"))
      (node (ref "SW4") (pin "3") (pinfunction "3_3") (pintype "passive"))
    )
    (net (code "21") (name "Net-(R28-Pad2)") (class "Default")
      (node (ref "R28") (pin "2") (pinfunction "2_2") (pintype "passive"))
      (node (ref "SW4") (pin "4") (pinfunction "4_4") (pintype "passive"))
    )
    (net (code "22") (name "Net-(R34-Pad2)") (class "Default")
      (node (ref "R34") (pin "2") (pinfunction "2_2") (pintype "passive"))
      (node (ref "SW5") (pin "3") (pinfunction "3_3") (pintype "passive"))
    )
    (net (code "23") (name "Net-(R35-Pad2)") (class "Default")
      (node (ref "R35") (pin "2") (pinfunction "2_2") (pintype "passive"))
      (node (ref "SW5") (pin "4") (pinfunction "4_4") (pintype "passive"))
    )
    (net (code "24") (name "Net-(R41-Pad2)") (class "Default")
      (node (ref "R41") (pin "2") (pinfunction "2_2") (pintype "passive"))
      (node (ref "SW6") (pin "3") (pinfunction "3_3") (pintype "passive"))
    )
    (net (code "25") (name "Net-(R42-Pad2)") (class "Default")
      (node (ref "R42") (pin "2") (pinfunction "2_2") (pintype "passive"))
      (node (ref "SW6") (pin "4") (pinfunction "4_4") (pintype "passive"))
    )
    (net (code "26") (name "Net-(R48-Pad2)") (class "Default")
      (node (ref "R48") (pin "2") (pinfunction "2_2") (pintype "passive"))
      (node (ref "SW7") (pin "3") (pinfunction "3_3") (pintype "passive"))
    )
    (net (code "27") (name "Net-(R49-Pad2)") (class "Default")
      (node (ref "R49") (pin "2") (pinfunction "2_2") (pintype "passive"))
      (node (ref "SW7") (pin "4") (pinfunction "4_4") (pintype "passive"))
    )
    (net (code "28") (name "Net-(R55-Pad2)") (class "Default")
      (node (ref "R55") (pin "2") (pinfunction "2_2") (pintype "passive"))
      (node (ref "SW8") (pin "3") (pinfunction "3_3") (pintype "passive"))
    )
    (net (code "29") (name "Net-(R56-Pad2)") (class "Default")
      (node (ref "R56") (pin "2") (pinfunction "2_2") (pintype "passive"))
      (node (ref "SW8") (pin "4") (pinfunction "4_4") (pintype "passive"))
    )
    (net (code "30") (name "Net-(R64-Pad2)") (class "Default")
      (node (ref "R64") (pin "2") (pinfunction "2_2") (pintype "passive"))
      (node (ref "SW9") (pin "16") (pinfunction "16_16") (pintype "passive"))
    )
    (net (code "31") (name "Net-(R74-Pad2)") (class "Default")
      (node (ref "R74") (pin "2") (pinfunction "2_2") (pintype "passive"))
      (node (ref "SW9") (pin "15") (pinfunction "15_15") (pintype "passive"))
    )
    (net (code "32") (name "Net-(R75-Pad2)") (class "Default")
      (node (ref "R75") (pin "2") (pinfunction "2_2") (pintype "passive"))
      (node (ref "SW9") (pin "14") (pinfunction "14_14") (pintype "passive"))
    )
    (net (code "33") (name "Net-(R76-Pad2)") (class "Default")
      (node (ref "R76") (pin "2") (pinfunction "2_2") (pintype "passive"))
      (node (ref "SW9") (pin "13") (pinfunction "13_13") (pintype "passive"))
    )
    (net (code "34") (name "Net-(R77-Pad2)") (class "Default")
      (node (ref "R77") (pin "2") (pinfunction "2_2") (pintype "passive"))
      (node (ref "SW9") (pin "12") (pinfunction "12_12") (pintype "passive"))
    )
    (net (code "35") (name "Net-(R78-Pad2)") (class "Default")
      (node (ref "R78") (pin "2") (pinfunction "2_2") (pintype "passive"))
      (node (ref "SW9") (pin "11") (pinfunction "11_11") (pintype "passive"))
    )
    (net (code "36") (name "Net-(R79-Pad2)") (class "Default")
      (node (ref "R79") (pin "2") (pinfunction "2_2") (pintype "passive"))
      (node (ref "SW9") (pin "10") (pinfunction "10_10") (pintype "passive"))
    )
    (net (code "37") (name "Net-(R80-Pad2)") (class "Default")
      (node (ref "R80") (pin "2") (pinfunction "2_2") (pintype "passive"))
      (node (ref "SW9") (pin "9") (pinfunction "9_9") (pintype "passive"))
    )
    (net (code "38") (name "Net-(TRIM_1-CW)") (class "Default")
      (node (ref "R3") (pin "1") (pinfunction "1_1") (pintype "passive"))
      (node (ref "TRIM_1") (pin "3") (pinfunction "CW_3") (pintype "passive"))
    )
    (net (code "39") (name "Net-(TRIM_2-CW)") (class "Default")
      (node (ref "R9") (pin "1") (pinfunction "1_1") (pintype "passive"))
      (node (ref "TRIM_2") (pin "3") (pinfunction "CW_3") (pintype "passive"))
    )
    (net (code "40") (name "Net-(TRIM_3-CW)") (class "Default")
      (node (ref "R16") (pin "1") (pinfunction "1_1") (pintype "passive"))
      (node (ref "TRIM_3") (pin "3") (pinfunction "CW_3") (pintype "passive"))
    )
    (net (code "41") (name "Net-(TRIM_4-CW)") (class "Default")
      (node (ref "R23") (pin "1") (pinfunction "1_1") (pintype "passive"))
      (node (ref "TRIM_4") (pin "3") (pinfunction "CW_3") (pintype "passive"))
    )
    (net (code "42") (name "Net-(TRIM_5-CW)") (class "Default")
      (node (ref "R30") (pin "1") (pinfunction "1_1") (pintype "passive"))
      (node (ref "TRIM_5") (pin "3") (pinfunction "CW_3") (pintype "passive"))
    )
    (net (code "43") (name "Net-(TRIM_6-CW)") (class "Default")
      (node (ref "R37") (pin "1") (pinfunction "1_1") (pintype "passive"))
      (node (ref "TRIM_6") (pin "3") (pinfunction "CW_3") (pintype "passive"))
    )
    (net (code "44") (name "Net-(TRIM_7-CW)") (class "Default")
      (node (ref "R44") (pin "1") (pinfunction "1_1") (pintype "passive"))
      (node (ref "TRIM_7") (pin "3") (pinfunction "CW_3") (pintype "passive"))
    )
    (net (code "45") (name "Net-(TRIM_8-CW)") (class "Default")
      (node (ref "R51") (pin "1") (pinfunction "1_1") (pintype "passive"))
      (node (ref "TRIM_8") (pin "3") (pinfunction "CW_3") (pintype "passive"))
    )
    (net (code "46") (name "Net-(U$2-Y)") (class "Default")
      (node (ref "R61") (pin "2") (pinfunction "2_2") (pintype "passive"))
      (node (ref "U$2") (pin "P$4") (pinfunction "Y_P$4") (pintype "bidirectional"))
    )
    (net (code "47") (name "Net-(U$20-B)") (class "Default")
      (node (ref "R61") (pin "1") (pinfunction "1_1") (pintype "passive"))
      (node (ref "U$20") (pin "P$2") (pinfunction "B_P$2") (pintype "passive"))
    )
    (net (code "48") (name "Net-(U$20-C)") (class "Default")
      (node (ref "R62") (pin "2") (pinfunction "2_2") (pintype "passive"))
      (node (ref "U$20") (pin "P$1") (pinfunction "C_P$1") (pintype "passive"))
    )
    (net (code "49") (name "Net-(U1-+IN)") (class "Default")
      (node (ref "R1") (pin "2") (pinfunction "2_2") (pintype "passive"))
      (node (ref "R4") (pin "1") (pinfunction "1_1") (pintype "passive"))
      (node (ref "U1") (pin "3") (pinfunction "+IN_3") (pintype "input"))
    )
    (net (code "50") (name "Net-(U1-RG)") (class "Default")
      (node (ref "C5") (pin "2") (pinfunction "2_2") (pintype "passive"))
      (node (ref "R2") (pin "2") (pinfunction "2_2") (pintype "passive"))
      (node (ref "R5") (pin "1") (pinfunction "1_1") (pintype "passive"))
      (node (ref "R6") (pin "1") (pinfunction "1_1") (pintype "passive"))
      (node (ref "R7") (pin "1") (pinfunction "1_1") (pintype "passive"))
      (node (ref "U1") (pin "6") (pinfunction "RG_6") (pintype "bidirectional"))
    )
    (net (code "51") (name "Net-(U2-+IN)") (class "Default")
      (node (ref "R10") (pin "1") (pinfunction "1_1") (pintype "passive"))
      (node (ref "R8") (pin "2") (pinfunction "2_2") (pintype "passive"))
      (node (ref "U2") (pin "3") (pinfunction "+IN_3") (pintype "input"))
    )
    (net (code "52") (name "Net-(U2-RG)") (class "Default")
      (node (ref "C7") (pin "2") (pinfunction "2_2") (pintype "passive"))
      (node (ref "R11") (pin "2") (pinfunction "2_2") (pintype "passive"))
      (node (ref "R12") (pin "1") (pinfunction "1_1") (pintype "passive"))
      (node (ref "R13") (pin "1") (pinfunction "1_1") (pintype "passive"))
      (node (ref "R14") (pin "1") (pinfunction "1_1") (pintype "passive"))
      (node (ref "U2") (pin "6") (pinfunction "RG_6") (pintype "bidirectional"))
    )
    (net (code "53") (name "Net-(U3-+IN)") (class "Default")
      (node (ref "R15") (pin "2") (pinfunction "2_2") (pintype "passive"))
      (node (ref "R17") (pin "1") (pinfunction "1_1") (pintype "passive"))
      (node (ref "U3") (pin "3") (pinfunction "+IN_3") (pintype "input"))
    )
    (net (code "54") (name "Net-(U3-RG)") (class "Default")
      (node (ref "C9") (pin "2") (pinfunction "2_2") (pintype "passive"))
      (node (ref "R18") (pin "2") (pinfunction "2_2") (pintype "passive"))
      (node (ref "R19") (pin "1") (pinfunction "1_1") (pintype "passive"))
      (node (ref "R20") (pin "1") (pinfunction "1_1") (pintype "passive"))
      (node (ref "R21") (pin "1") (pinfunction "1_1") (pintype "passive"))
      (node (ref "U3") (pin "6") (pinfunction "RG_6") (pintype "bidirectional"))
    )
    (net (code "55") (name "Net-(U4-+IN)") (class "Default")
      (node (ref "R22") (pin "2") (pinfunction "2_2") (pintype "passive"))
      (node (ref "R24") (pin "1") (pinfunction "1_1") (pintype "passive"))
      (node (ref "U4") (pin "3") (pinfunction "+IN_3") (pintype "input"))
    )
    (net (code "56") (name "Net-(U4-RG)") (class "Default")
      (node (ref "C11") (pin "2") (pinfunction "2_2") (pintype "passive"))
      (node (ref "R25") (pin "2") (pinfunction "2_2") (pintype "passive"))
      (node (ref "R26") (pin "1") (pinfunction "1_1") (pintype "passive"))
      (node (ref "R27") (pin "1") (pinfunction "1_1") (pintype "passive"))
      (node (ref "R28") (pin "1") (pinfunction "1_1") (pintype "passive"))
      (node (ref "U4") (pin "6") (pinfunction "RG_6") (pintype "bidirectional"))
    )
    (net (code "57") (name "Net-(U5-+IN)") (class "Default")
      (node (ref "R29") (pin "2") (pinfunction "2_2") (pintype "passive"))
      (node (ref "R31") (pin "1") (pinfunction "1_1") (pintype "passive"))
      (node (ref "U5") (pin "3") (pinfunction "+IN_3") (pintype "input"))
    )
    (net (code "58") (name "Net-(U5-RG)") (class "Default")
      (node (ref "C13") (pin "2") (pinfunction "2_2") (pintype "passive"))
      (node (ref "R32") (pin "2") (pinfunction "2_2") (pintype "passive"))
      (node (ref "R33") (pin "1") (pinfunction "1_1") (pintype "passive"))
      (node (ref "R34") (pin "1") (pinfunction "1_1") (pintype "passive"))
      (node (ref "R35") (pin "1") (pinfunction "1_1") (pintype "passive"))
      (node (ref "U5") (pin "6") (pinfunction "RG_6") (pintype "bidirectional"))
    )
    (net (code "59") (name "Net-(U6-+IN)") (class "Default")
      (node (ref "R36") (pin "2") (pinfunction "2_2") (pintype "passive"))
      (node (ref "R38") (pin "1") (pinfunction "1_1") (pintype "passive"))
      (node (ref "U6") (pin "3") (pinfunction "+IN_3") (pintype "input"))
    )
    (net (code "60") (name "Net-(U6-RG)") (class "Default")
      (node (ref "C15") (pin "2") (pinfunction "2_2") (pintype "passive"))
      (node (ref "R39") (pin "2") (pinfunction "2_2") (pintype "passive"))
      (node (ref "R40") (pin "1") (pinfunction "1_1") (pintype "passive"))
      (node (ref "R41") (pin "1") (pinfunction "1_1") (pintype "passive"))
      (node (ref "R42") (pin "1") (pinfunction "1_1") (pintype "passive"))
      (node (ref "U6") (pin "6") (pinfunction "RG_6") (pintype "bidirectional"))
    )
    (net (code "61") (name "Net-(U7-+IN)") (class "Default")
      (node (ref "R43") (pin "2") (pinfunction "2_2") (pintype "passive"))
      (node (ref "R45") (pin "1") (pinfunction "1_1") (pintype "passive"))
      (node (ref "U7") (pin "3") (pinfunction "+IN_3") (pintype "input"))
    )
    (net (code "62") (name "Net-(U7-RG)") (class "Default")
      (node (ref "C17") (pin "2") (pinfunction "2_2") (pintype "passive"))
      (node (ref "R46") (pin "2") (pinfunction "2_2") (pintype "passive"))
      (node (ref "R47") (pin "1") (pinfunction "1_1") (pintype "passive"))
      (node (ref "R48") (pin "1") (pinfunction "1_1") (pintype "passive"))
      (node (ref "R49") (pin "1") (pinfunction "1_1") (pintype "passive"))
      (node (ref "U7") (pin "6") (pinfunction "RG_6") (pintype "bidirectional"))
    )
    (net (code "63") (name "Net-(U8-+IN)") (class "Default")
      (node (ref "R50") (pin "2") (pinfunction "2_2") (pintype "passive"))
      (node (ref "R52") (pin "1") (pinfunction "1_1") (pintype "passive"))
      (node (ref "U8") (pin "3") (pinfunction "+IN_3") (pintype "input"))
    )
    (net (code "64") (name "Net-(U8-RG)") (class "Default")
      (node (ref "C19") (pin "2") (pinfunction "2_2") (pintype "passive"))
      (node (ref "R53") (pin "2") (pinfunction "2_2") (pintype "passive"))
      (node (ref "R54") (pin "1") (pinfunction "1_1") (pintype "passive"))
      (node (ref "R55") (pin "1") (pinfunction "1_1") (pintype "passive"))
      (node (ref "R56") (pin "1") (pinfunction "1_1") (pintype "passive"))
      (node (ref "U8") (pin "6") (pinfunction "RG_6") (pintype "bidirectional"))
    )
    (net (code "65") (name "OUT1") (class "Default")
      (node (ref "C5") (pin "1") (pinfunction "1_1") (pintype "passive"))
      (node (ref "OUTPUTS") (pin "15") (pinfunction "8_15") (pintype "bidirectional"))
      (node (ref "OUTPUTS") (pin "16") (pinfunction "8_16") (pintype "bidirectional"))
      (node (ref "R5") (pin "2") (pinfunction "2_2") (pintype "passive"))
      (node (ref "SW1") (pin "1") (pinfunction "1_1") (pintype "passive"))
      (node (ref "SW1") (pin "2") (pinfunction "2_2") (pintype "passive"))
      (node (ref "SW9") (pin "1") (pinfunction "1_1") (pintype "passive"))
      (node (ref "U1") (pin "7") (pinfunction "OUT_7") (pintype "output"))
    )
    (net (code "66") (name "OUT2") (class "Default")
      (node (ref "C7") (pin "1") (pinfunction "1_1") (pintype "passive"))
      (node (ref "OUTPUTS") (pin "13") (pinfunction "7_13") (pintype "bidirectional"))
      (node (ref "OUTPUTS") (pin "14") (pinfunction "7_14") (pintype "bidirectional"))
      (node (ref "R12") (pin "2") (pinfunction "2_2") (pintype "passive"))
      (node (ref "SW2") (pin "1") (pinfunction "1_1") (pintype "passive"))
      (node (ref "SW2") (pin "2") (pinfunction "2_2") (pintype "passive"))
      (node (ref "SW9") (pin "2") (pinfunction "2_2") (pintype "passive"))
      (node (ref "U2") (pin "7") (pinfunction "OUT_7") (pintype "output"))
    )
    (net (code "67") (name "OUT3") (class "Default")
      (node (ref "C9") (pin "1") (pinfunction "1_1") (pintype "passive"))
      (node (ref "OUTPUTS") (pin "11") (pinfunction "6_11") (pintype "bidirectional"))
      (node (ref "OUTPUTS") (pin "12") (pinfunction "6_12") (pintype "bidirectional"))
      (node (ref "R19") (pin "2") (pinfunction "2_2") (pintype "passive"))
      (node (ref "SW3") (pin "1") (pinfunction "1_1") (pintype "passive"))
      (node (ref "SW3") (pin "2") (pinfunction "2_2") (pintype "passive"))
      (node (ref "SW9") (pin "3") (pinfunction "3_3") (pintype "passive"))
      (node (ref "U3") (pin "7") (pinfunction "OUT_7") (pintype "output"))
    )
    (net (code "68") (name "OUT4") (class "Default")
      (node (ref "C11") (pin "1") (pinfunction "1_1") (pintype "passive"))
      (node (ref "OUTPUTS") (pin "10") (pinfunction "5_10") (pintype "bidirectional"))
      (node (ref "OUTPUTS") (pin "9") (pinfunction "5_9") (pintype "bidirectional"))
      (node (ref "R26") (pin "2") (pinfunction "2_2") (pintype "passive"))
      (node (ref "SW4") (pin "1") (pinfunction "1_1") (pintype "passive"))
      (node (ref "SW4") (pin "2") (pinfunction "2_2") (pintype "passive"))
      (node (ref "SW9") (pin "4") (pinfunction "4_4") (pintype "passive"))
      (node (ref "U4") (pin "7") (pinfunction "OUT_7") (pintype "output"))
    )
    (net (code "69") (name "OUT5") (class "Default")
      (node (ref "C13") (pin "1") (pinfunction "1_1") (pintype "passive"))
      (node (ref "OUTPUTS") (pin "7") (pinfunction "4_7") (pintype "bidirectional"))
      (node (ref "OUTPUTS") (pin "8") (pinfunction "4_8") (pintype "bidirectional"))
      (node (ref "R33") (pin "2") (pinfunction "2_2") (pintype "passive"))
      (node (ref "SW5") (pin "1") (pinfunction "1_1") (pintype "passive"))
      (node (ref "SW5") (pin "2") (pinfunction "2_2") (pintype "passive"))
      (node (ref "SW9") (pin "5") (pinfunction "5_5") (pintype "passive"))
      (node (ref "U5") (pin "7") (pinfunction "OUT_7") (pintype "output"))
    )
    (net (code "70") (name "OUT6") (class "Default")
      (node (ref "C15") (pin "1") (pinfunction "1_1") (pintype "passive"))
      (node (ref "OUTPUTS") (pin "5") (pinfunction "3_5") (pintype "bidirectional"))
      (node (ref "OUTPUTS") (pin "6") (pinfunction "3_6") (pintype "bidirectional"))
      (node (ref "R40") (pin "2") (pinfunction "2_2") (pintype "passive"))
      (node (ref "SW6") (pin "1") (pinfunction "1_1") (pintype "passive"))
      (node (ref "SW6") (pin "2") (pinfunction "2_2") (pintype "passive"))
      (node (ref "SW9") (pin "6") (pinfunction "6_6") (pintype "passive"))
      (node (ref "U6") (pin "7") (pinfunction "OUT_7") (pintype "output"))
    )
    (net (code "71") (name "OUT7") (class "Default")
      (node (ref "C17") (pin "1") (pinfunction "1_1") (pintype "passive"))
      (node (ref "OUTPUTS") (pin "3") (pinfunction "2_3") (pintype "bidirectional"))
      (node (ref "OUTPUTS") (pin "4") (pinfunction "2_4") (pintype "bidirectional"))
      (node (ref "R47") (pin "2") (pinfunction "2_2") (pintype "passive"))
      (node (ref "SW7") (pin "1") (pinfunction "1_1") (pintype "passive"))
      (node (ref "SW7") (pin "2") (pinfunction "2_2") (pintype "passive"))
      (node (ref "SW9") (pin "7") (pinfunction "7_7") (pintype "passive"))
      (node (ref "U7") (pin "7") (pinfunction "OUT_7") (pintype "output"))
    )
    (net (code "72") (name "OUT8") (class "Default")
      (node (ref "C19") (pin "1") (pinfunction "1_1") (pintype "passive"))
      (node (ref "OUTPUTS") (pin "1") (pinfunction "1_1") (pintype "bidirectional"))
      (node (ref "OUTPUTS") (pin "2") (pinfunction "1_2") (pintype "bidirectional"))
      (node (ref "R54") (pin "2") (pinfunction "2_2") (pintype "passive"))
      (node (ref "SW8") (pin "1") (pinfunction "1_1") (pintype "passive"))
      (node (ref "SW8") (pin "2") (pinfunction "2_2") (pintype "passive"))
      (node (ref "SW9") (pin "8") (pinfunction "8_8") (pintype "passive"))
      (node (ref "U8") (pin "7") (pinfunction "OUT_7") (pintype "output"))
    )
    (net (code "73") (name "SG_1") (class "Default")
      (node (ref "SG_CONN") (pin "1") (pinfunction "1_1") (pintype "bidirectional"))
      (node (ref "SG_CONN") (pin "2") (pinfunction "1_2") (pintype "bidirectional"))
      (node (ref "TRIM_1") (pin "2") (pinfunction "WIPER_2") (pintype "passive"))
      (node (ref "U1") (pin "2") (pinfunction "-IN_2") (pintype "input"))
    )
    (net (code "74") (name "SG_2") (class "Default")
      (node (ref "SG_CONN") (pin "5") (pinfunction "3_5") (pintype "bidirectional"))
      (node (ref "SG_CONN") (pin "6") (pinfunction "3_6") (pintype "bidirectional"))
      (node (ref "TRIM_2") (pin "2") (pinfunction "WIPER_2") (pintype "passive"))
      (node (ref "U2") (pin "2") (pinfunction "-IN_2") (pintype "input"))
    )
    (net (code "75") (name "SG_3") (class "Default")
      (node (ref "SG_CONN") (pin "10") (pinfunction "5_10") (pintype "bidirectional"))
      (node (ref "SG_CONN") (pin "9") (pinfunction "5_9") (pintype "bidirectional"))
      (node (ref "TRIM_3") (pin "2") (pinfunction "WIPER_2") (pintype "passive"))
      (node (ref "U3") (pin "2") (pinfunction "-IN_2") (pintype "input"))
    )
    (net (code "76") (name "SG_4") (class "Default")
      (node (ref "SG_CONN") (pin "13") (pinfunction "7_13") (pintype "bidirectional"))
      (node (ref "SG_CONN") (pin "14") (pinfunction "7_14") (pintype "bidirectional"))
      (node (ref "TRIM_4") (pin "2") (pinfunction "WIPER_2") (pintype "passive"))
      (node (ref "U4") (pin "2") (pinfunction "-IN_2") (pintype "input"))
    )
    (net (code "77") (name "SG_5") (class "Default")
      (node (ref "SG_CONN") (pin "17") (pinfunction "9_17") (pintype "bidirectional"))
      (node (ref "SG_CONN") (pin "18") (pinfunction "9_18") (pintype "bidirectional"))
      (node (ref "TRIM_5") (pin "2") (pinfunction "WIPER_2") (pintype "passive"))
      (node (ref "U5") (pin "2") (pinfunction "-IN_2") (pintype "input"))
    )
    (net (code "78") (name "SG_6") (class "Default")
      (node (ref "SG_CONN") (pin "21") (pinfunction "11_21") (pintype "bidirectional"))
      (node (ref "SG_CONN") (pin "22") (pinfunction "11_22") (pintype "bidirectional"))
      (node (ref "TRIM_6") (pin "2") (pinfunction "WIPER_2") (pintype "passive"))
      (node (ref "U6") (pin "2") (pinfunction "-IN_2") (pintype "input"))
    )
    (net (code "79") (name "SG_7") (class "Default")
      (node (ref "SG_CONN") (pin "25") (pinfunction "13_25") (pintype "bidirectional"))
      (node (ref "SG_CONN") (pin "26") (pinfunction "13_26") (pintype "bidirectional"))
      (node (ref "TRIM_7") (pin "2") (pinfunction "WIPER_2") (pintype "passive"))
      (node (ref "U7") (pin "2") (pinfunction "-IN_2") (pintype "input"))
    )
    (net (code "80") (name "SG_8") (class "Default")
      (node (ref "SG_CONN") (pin "29") (pinfunction "15_29") (pintype "bidirectional"))
      (node (ref "SG_CONN") (pin "30") (pinfunction "15_30") (pintype "bidirectional"))
      (node (ref "TRIM_8") (pin "2") (pinfunction "WIPER_2") (pintype "passive"))
      (node (ref "U8") (pin "2") (pinfunction "-IN_2") (pintype "input"))
    )
    (net (code "81") (name "UPP_V") (class "Default")
      (node (ref "IC1") (pin "5") (pinfunction "+IN_5") (pintype "input"))
      (node (ref "R59") (pin "1") (pinfunction "1_1") (pintype "passive"))
      (node (ref "R60") (pin "2") (pinfunction "2_2") (pintype "passive"))
    )
    (net (code "82") (name "unconnected-(TRIM_1-CCW-Pad1)") (class "Default")
      (node (ref "TRIM_1") (pin "1") (pinfunction "CCW_1") (pintype "passive"))
    )
    (net (code "83") (name "unconnected-(TRIM_2-CCW-Pad1)") (class "Default")
      (node (ref "TRIM_2") (pin "1") (pinfunction "CCW_1") (pintype "passive"))
    )
    (net (code "84") (name "unconnected-(TRIM_3-CCW-Pad1)") (class "Default")
      (node (ref "TRIM_3") (pin "1") (pinfunction "CCW_1") (pintype "passive"))
    )
    (net (code "85") (name "unconnected-(TRIM_4-CCW-Pad1)") (class "Default")
      (node (ref "TRIM_4") (pin "1") (pinfunction "CCW_1") (pintype "passive"))
    )
    (net (code "86") (name "unconnected-(TRIM_5-CCW-Pad1)") (class "Default")
      (node (ref "TRIM_5") (pin "1") (pinfunction "CCW_1") (pintype "passive"))
    )
    (net (code "87") (name "unconnected-(TRIM_6-CCW-Pad1)") (class "Default")
      (node (ref "TRIM_6") (pin "1") (pinfunction "CCW_1") (pintype "passive"))
    )
    (net (code "88") (name "unconnected-(TRIM_7-CCW-Pad1)") (class "Default")
      (node (ref "TRIM_7") (pin "1") (pinfunction "CCW_1") (pintype "passive"))
    )
    (net (code "89") (name "unconnected-(TRIM_8-CCW-Pad1)") (class "Default")
      (node (ref "TRIM_8") (pin "1") (pinfunction "CCW_1") (pintype "passive"))
    )
  )
)
